# Display_Schematic.net
KiCad netlist of a schematic drawn in Altium Designer
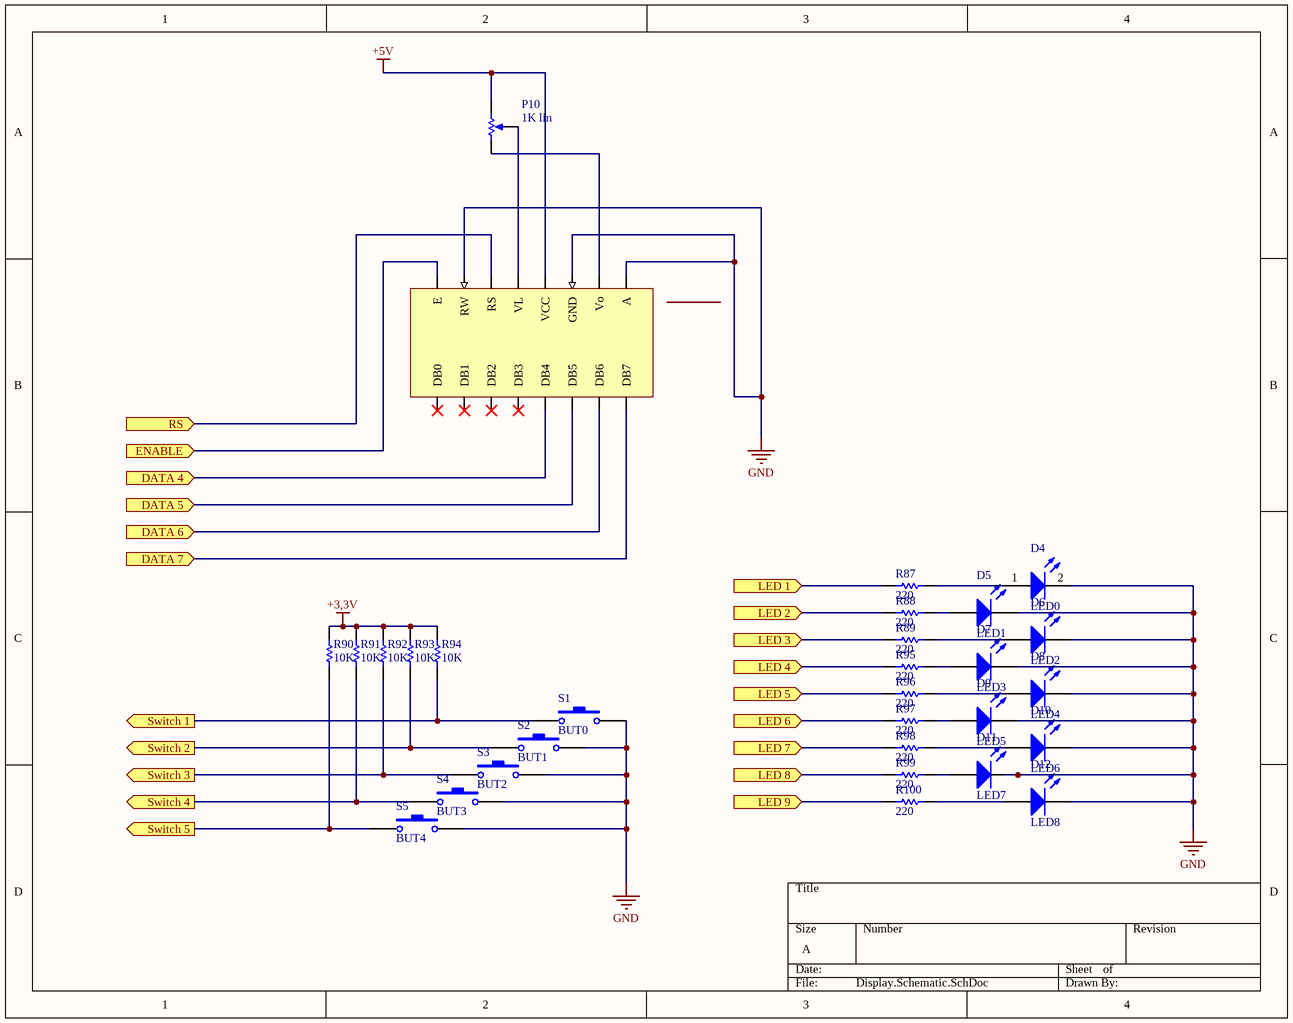
[diagram p0: Display.Schematic.SchDoc]

(export (version "E")
  (design (tool "Eeschema 10.0.6"))
  (components
    (comp (ref "D4")
      (value "LED0")
      (footprint "LED")
      (description "Typical INFRARED GaAs LED")
      (fields (field (name "PUBLISHER") "Altium Limited"))
      (libsource (lib "") (part "LED0_1"))
    )
    (comp (ref "D5")
      (value "LED1")
      (footprint "LED")
      (description "Typical INFRARED GaAs LED")
      (fields (field (name "PUBLISHER") "Altium Limited"))
      (libsource (lib "Miscellaneous Devices") (part "LED0"))
    )
    (comp (ref "D6")
      (value "LED2")
      (footprint "LED")
      (description "Typical INFRARED GaAs LED")
      (fields (field (name "PUBLISHER") "Altium Limited"))
      (libsource (lib "Miscellaneous Devices") (part "LED0"))
    )
    (comp (ref "D7")
      (value "LED3")
      (footprint "LED")
      (description "Typical INFRARED GaAs LED")
      (fields (field (name "PUBLISHER") "Altium Limited"))
      (libsource (lib "Miscellaneous Devices") (part "LED0"))
    )
    (comp (ref "D8")
      (value "LED4")
      (footprint "LED")
      (description "Typical INFRARED GaAs LED")
      (fields (field (name "PUBLISHER") "Altium Limited"))
      (libsource (lib "Miscellaneous Devices") (part "LED0"))
    )
    (comp (ref "D9")
      (value "LED5")
      (footprint "LED")
      (description "Typical INFRARED GaAs LED")
      (fields (field (name "PUBLISHER") "Altium Limited"))
      (libsource (lib "Miscellaneous Devices") (part "LED0"))
    )
    (comp (ref "D10")
      (value "LED6")
      (footprint "LED")
      (description "Typical INFRARED GaAs LED")
      (fields (field (name "PUBLISHER") "Altium Limited"))
      (libsource (lib "Miscellaneous Devices") (part "LED0"))
    )
    (comp (ref "D11")
      (value "LED7")
      (footprint "LED")
      (description "Typical INFRARED GaAs LED")
      (fields (field (name "PUBLISHER") "Altium Limited"))
      (libsource (lib "Miscellaneous Devices") (part "LED0"))
    )
    (comp (ref "D12")
      (value "LED8")
      (footprint "LED")
      (description "Typical INFRARED GaAs LED")
      (fields (field (name "PUBLISHER") "Altium Limited"))
      (libsource (lib "Miscellaneous Devices") (part "LED0"))
    )
    (comp (ref "Display1")
      (value "16x2 LCD")
      (footprint "Display")
      (libsource (lib "display") (part "Display"))
    )
    (comp (ref "P10")
      (value "1K lin")
      (footprint "BOURNS Trim pot")
      (description "Potentiometer")
      (fields (field (name "PUBLISHER") "Altium Limited"))
      (libsource (lib "Miscellaneous Devices") (part "RPot"))
    )
    (comp (ref "R87")
      (value "220")
      (footprint "CAPC1608N")
      (description "Resistor")
      (fields (field (name "PUBLISHER") "Altium Limited"))
      (libsource (lib "Miscellaneous Devices") (part "Res1"))
    )
    (comp (ref "R88")
      (value "220")
      (footprint "CAPC1608N")
      (description "Resistor")
      (fields (field (name "PUBLISHER") "Altium Limited"))
      (libsource (lib "Miscellaneous Devices") (part "Res1"))
    )
    (comp (ref "R89")
      (value "220")
      (footprint "CAPC1608N")
      (description "Resistor")
      (fields (field (name "PUBLISHER") "Altium Limited"))
      (libsource (lib "Miscellaneous Devices") (part "Res1"))
    )
    (comp (ref "R90")
      (value "10K")
      (footprint "CAPC1608N")
      (description "Resistor")
      (fields (field (name "PUBLISHER") "Altium Limited"))
      (libsource (lib "Miscellaneous Devices") (part "Res1"))
    )
    (comp (ref "R91")
      (value "10K")
      (footprint "CAPC1608N")
      (description "Resistor")
      (fields (field (name "PUBLISHER") "Altium Limited"))
      (libsource (lib "Miscellaneous Devices") (part "Res1"))
    )
    (comp (ref "R92")
      (value "10K")
      (footprint "CAPC1608N")
      (description "Resistor")
      (fields (field (name "PUBLISHER") "Altium Limited"))
      (libsource (lib "Miscellaneous Devices") (part "Res1"))
    )
    (comp (ref "R93")
      (value "10K")
      (footprint "CAPC1608N")
      (description "Resistor")
      (fields (field (name "PUBLISHER") "Altium Limited"))
      (libsource (lib "Miscellaneous Devices") (part "Res1"))
    )
    (comp (ref "R94")
      (value "10K")
      (footprint "CAPC1608N")
      (description "Resistor")
      (fields (field (name "PUBLISHER") "Altium Limited"))
      (libsource (lib "Miscellaneous Devices") (part "Res1"))
    )
    (comp (ref "R95")
      (value "220")
      (footprint "CAPC1608N")
      (description "Resistor")
      (fields (field (name "PUBLISHER") "Altium Limited"))
      (libsource (lib "Miscellaneous Devices") (part "Res1"))
    )
    (comp (ref "R96")
      (value "220")
      (footprint "CAPC1608N")
      (description "Resistor")
      (fields (field (name "PUBLISHER") "Altium Limited"))
      (libsource (lib "Miscellaneous Devices") (part "Res1"))
    )
    (comp (ref "R97")
      (value "220")
      (footprint "CAPC1608N")
      (description "Resistor")
      (fields (field (name "PUBLISHER") "Altium Limited"))
      (libsource (lib "Miscellaneous Devices") (part "Res1"))
    )
    (comp (ref "R98")
      (value "220")
      (footprint "CAPC1608N")
      (description "Resistor")
      (fields (field (name "PUBLISHER") "Altium Limited"))
      (libsource (lib "Miscellaneous Devices") (part "Res1"))
    )
    (comp (ref "R99")
      (value "220")
      (footprint "CAPC1608N")
      (description "Resistor")
      (fields (field (name "PUBLISHER") "Altium Limited"))
      (libsource (lib "Miscellaneous Devices") (part "Res1"))
    )
    (comp (ref "R100")
      (value "220")
      (footprint "CAPC1608N")
      (description "Resistor")
      (fields (field (name "PUBLISHER") "Altium Limited"))
      (libsource (lib "Miscellaneous Devices") (part "Res1"))
    )
    (comp (ref "S1")
      (value "BUT0")
      (footprint "PUSH BUTTON")
      (description "Switch")
      (fields (field (name "PUBLISHER") "Altium Limited"))
      (libsource (lib "Miscellaneous Devices") (part "SW-PB"))
    )
    (comp (ref "S2")
      (value "BUT1")
      (footprint "PUSH BUTTON")
      (description "Switch")
      (fields (field (name "PUBLISHER") "Altium Limited"))
      (libsource (lib "Miscellaneous Devices") (part "SW-PB"))
    )
    (comp (ref "S3")
      (value "BUT2")
      (footprint "PUSH BUTTON")
      (description "Switch")
      (fields (field (name "PUBLISHER") "Altium Limited"))
      (libsource (lib "Miscellaneous Devices") (part "SW-PB"))
    )
    (comp (ref "S4")
      (value "BUT3")
      (footprint "PUSH BUTTON")
      (description "Switch")
      (fields (field (name "PUBLISHER") "Altium Limited"))
      (libsource (lib "Miscellaneous Devices") (part "SW-PB"))
    )
    (comp (ref "S5")
      (value "BUT4")
      (footprint "PUSH BUTTON")
      (description "Switch")
      (fields (field (name "PUBLISHER") "Altium Limited"))
      (libsource (lib "Miscellaneous Devices") (part "SW-PB"))
    )
  )
  (nets
    (net (code "1") (name "+3,3V") (class "Default")
      (node (ref "R90") (pin "2") (pinfunction "2_2") (pintype "passive"))
      (node (ref "R91") (pin "2") (pinfunction "2_2") (pintype "passive"))
      (node (ref "R92") (pin "2") (pinfunction "2_2") (pintype "passive"))
      (node (ref "R93") (pin "2") (pinfunction "2_2") (pintype "passive"))
      (node (ref "R94") (pin "2") (pinfunction "2_2") (pintype "passive"))
    )
    (net (code "2") (name "+5V") (class "Default")
      (node (ref "Display1") (pin "2") (pinfunction "VCC_2") (pintype "passive"))
      (node (ref "P10") (pin "2") (pinfunction "BOT_2") (pintype "passive"))
    )
    (net (code "3") (name "/DATA 4") (class "Default")
      (node (ref "Display1") (pin "10") (pinfunction "DB4_10") (pintype "passive"))
    )
    (net (code "4") (name "/DATA 5") (class "Default")
      (node (ref "Display1") (pin "9") (pinfunction "DB5_9") (pintype "passive"))
    )
    (net (code "5") (name "/DATA 6") (class "Default")
      (node (ref "Display1") (pin "8") (pinfunction "DB6_8") (pintype "passive"))
    )
    (net (code "6") (name "/DATA 7") (class "Default")
      (node (ref "Display1") (pin "7") (pinfunction "DB7_7") (pintype "passive"))
    )
    (net (code "7") (name "/ENABLE") (class "Default")
      (node (ref "Display1") (pin "6") (pinfunction "E_6") (pintype "passive"))
    )
    (net (code "8") (name "/LED 1") (class "Default")
      (node (ref "R87") (pin "1") (pinfunction "1_1") (pintype "passive"))
    )
    (net (code "9") (name "/LED 2") (class "Default")
      (node (ref "R88") (pin "1") (pinfunction "1_1") (pintype "passive"))
    )
    (net (code "10") (name "/LED 3") (class "Default")
      (node (ref "R89") (pin "1") (pinfunction "1_1") (pintype "passive"))
    )
    (net (code "11") (name "/LED 4") (class "Default")
      (node (ref "R95") (pin "1") (pinfunction "1_1") (pintype "passive"))
    )
    (net (code "12") (name "/LED 5") (class "Default")
      (node (ref "R96") (pin "1") (pinfunction "1_1") (pintype "passive"))
    )
    (net (code "13") (name "/LED 6") (class "Default")
      (node (ref "R97") (pin "1") (pinfunction "1_1") (pintype "passive"))
    )
    (net (code "14") (name "/LED 7") (class "Default")
      (node (ref "R98") (pin "1") (pinfunction "1_1") (pintype "passive"))
    )
    (net (code "15") (name "/LED 8") (class "Default")
      (node (ref "R99") (pin "1") (pinfunction "1_1") (pintype "passive"))
    )
    (net (code "16") (name "/LED 9") (class "Default")
      (node (ref "R100") (pin "1") (pinfunction "1_1") (pintype "passive"))
    )
    (net (code "17") (name "/RS") (class "Default")
      (node (ref "Display1") (pin "4") (pinfunction "RS_4") (pintype "passive"))
    )
    (net (code "18") (name "/Switch 1") (class "Default")
      (node (ref "R94") (pin "1") (pinfunction "1_1") (pintype "passive"))
      (node (ref "S1") (pin "1") (pinfunction "1_1") (pintype "passive"))
    )
    (net (code "19") (name "/Switch 2") (class "Default")
      (node (ref "R93") (pin "1") (pinfunction "1_1") (pintype "passive"))
      (node (ref "S2") (pin "1") (pinfunction "1_1") (pintype "passive"))
    )
    (net (code "20") (name "/Switch 3") (class "Default")
      (node (ref "R92") (pin "1") (pinfunction "1_1") (pintype "passive"))
      (node (ref "S3") (pin "1") (pinfunction "1_1") (pintype "passive"))
    )
    (net (code "21") (name "/Switch 4") (class "Default")
      (node (ref "R91") (pin "1") (pinfunction "1_1") (pintype "passive"))
      (node (ref "S4") (pin "1") (pinfunction "1_1") (pintype "passive"))
    )
    (net (code "22") (name "/Switch 5") (class "Default")
      (node (ref "R90") (pin "1") (pinfunction "1_1") (pintype "passive"))
      (node (ref "S5") (pin "1") (pinfunction "1_1") (pintype "passive"))
    )
    (net (code "23") (name "GND") (class "Default")
      (node (ref "D10") (pin "2") (pinfunction "K_2") (pintype "passive"))
      (node (ref "D11") (pin "2") (pinfunction "K_2") (pintype "passive"))
      (node (ref "D12") (pin "2") (pinfunction "K_2") (pintype "passive"))
      (node (ref "D4") (pin "2") (pinfunction "K_2") (pintype "passive"))
      (node (ref "D5") (pin "2") (pinfunction "K_2") (pintype "passive"))
      (node (ref "D6") (pin "2") (pinfunction "K_2") (pintype "passive"))
      (node (ref "D7") (pin "2") (pinfunction "K_2") (pintype "passive"))
      (node (ref "D8") (pin "2") (pinfunction "K_2") (pintype "passive"))
      (node (ref "D9") (pin "2") (pinfunction "K_2") (pintype "passive"))
      (node (ref "Display1") (pin "1") (pinfunction "GND_1") (pintype "input"))
      (node (ref "Display1") (pin "16") (pinfunction "A_16") (pintype "passive"))
      (node (ref "Display1") (pin "5") (pinfunction "RW_5") (pintype "input"))
      (node (ref "S1") (pin "2") (pinfunction "2_2") (pintype "passive"))
      (node (ref "S2") (pin "2") (pinfunction "2_2") (pintype "passive"))
      (node (ref "S3") (pin "2") (pinfunction "2_2") (pintype "passive"))
      (node (ref "S4") (pin "2") (pinfunction "2_2") (pintype "passive"))
      (node (ref "S5") (pin "2") (pinfunction "2_2") (pintype "passive"))
    )
    (net (code "24") (name "Net-(D4-A)") (class "Default")
      (node (ref "D4") (pin "1") (pinfunction "A_1") (pintype "passive"))
      (node (ref "R87") (pin "2") (pinfunction "2_2") (pintype "passive"))
    )
    (net (code "25") (name "Net-(D5-A)") (class "Default")
      (node (ref "D5") (pin "1") (pinfunction "A_1") (pintype "passive"))
      (node (ref "R88") (pin "2") (pinfunction "2_2") (pintype "passive"))
    )
    (net (code "26") (name "Net-(D6-A)") (class "Default")
      (node (ref "D6") (pin "1") (pinfunction "A_1") (pintype "passive"))
      (node (ref "R89") (pin "2") (pinfunction "2_2") (pintype "passive"))
    )
    (net (code "27") (name "Net-(D7-A)") (class "Default")
      (node (ref "D7") (pin "1") (pinfunction "A_1") (pintype "passive"))
      (node (ref "R95") (pin "2") (pinfunction "2_2") (pintype "passive"))
    )
    (net (code "28") (name "Net-(D8-A)") (class "Default")
      (node (ref "D8") (pin "1") (pinfunction "A_1") (pintype "passive"))
      (node (ref "R96") (pin "2") (pinfunction "2_2") (pintype "passive"))
    )
    (net (code "29") (name "Net-(D9-A)") (class "Default")
      (node (ref "D9") (pin "1") (pinfunction "A_1") (pintype "passive"))
      (node (ref "R97") (pin "2") (pinfunction "2_2") (pintype "passive"))
    )
    (net (code "30") (name "Net-(D10-A)") (class "Default")
      (node (ref "D10") (pin "1") (pinfunction "A_1") (pintype "passive"))
      (node (ref "R98") (pin "2") (pinfunction "2_2") (pintype "passive"))
    )
    (net (code "31") (name "Net-(D11-A)") (class "Default")
      (node (ref "D11") (pin "1") (pinfunction "A_1") (pintype "passive"))
      (node (ref "R99") (pin "2") (pinfunction "2_2") (pintype "passive"))
    )
    (net (code "32") (name "Net-(D12-A)") (class "Default")
      (node (ref "D12") (pin "1") (pinfunction "A_1") (pintype "passive"))
      (node (ref "R100") (pin "2") (pinfunction "2_2") (pintype "passive"))
    )
    (net (code "33") (name "Net-(Display1-VL)") (class "Default")
      (node (ref "Display1") (pin "3") (pinfunction "VL_3") (pintype "passive"))
      (node (ref "P10") (pin "3") (pinfunction "TAP_3") (pintype "passive"))
    )
    (net (code "34") (name "Net-(Display1-Vo)") (class "Default")
      (node (ref "Display1") (pin "15") (pinfunction "Vo_15") (pintype "passive"))
      (node (ref "P10") (pin "1") (pinfunction "TOP_1") (pintype "passive"))
    )
    (net (code "35") (name "unconnected-(Display1-DB0-Pad14)") (class "Default")
      (node (ref "Display1") (pin "14") (pinfunction "DB0_14") (pintype "passive+no_connect"))
    )
    (net (code "36") (name "unconnected-(Display1-DB1-Pad13)") (class "Default")
      (node (ref "Display1") (pin "13") (pinfunction "DB1_13") (pintype "passive+no_connect"))
    )
    (net (code "37") (name "unconnected-(Display1-DB2-Pad12)") (class "Default")
      (node (ref "Display1") (pin "12") (pinfunction "DB2_12") (pintype "passive+no_connect"))
    )
    (net (code "38") (name "unconnected-(Display1-DB3-Pad11)") (class "Default")
      (node (ref "Display1") (pin "11") (pinfunction "DB3_11") (pintype "passive+no_connect"))
    )
  )
)
